# MCU.net
KiCad netlist of a schematic drawn in Altium Designer
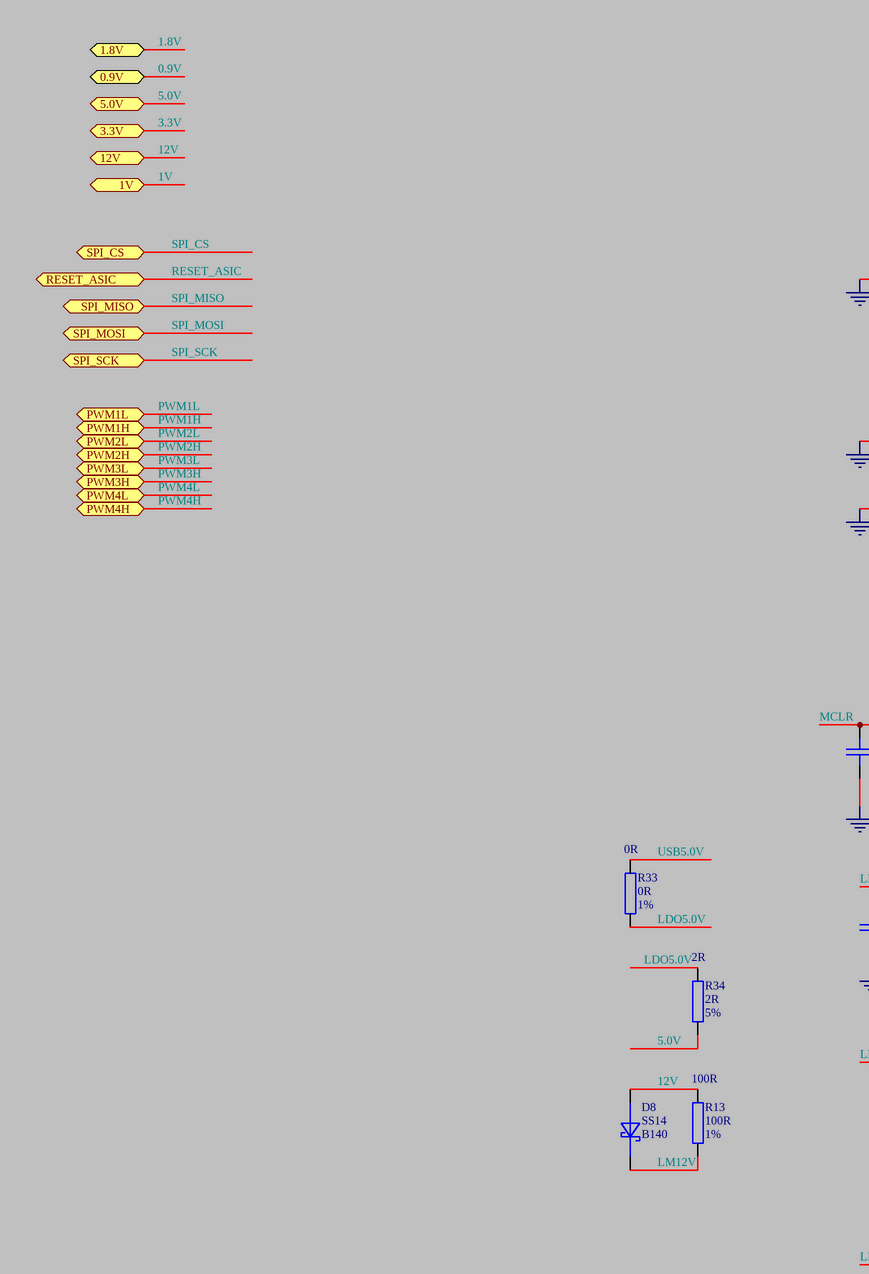
[diagram p0: MCU.SchDoc, left]
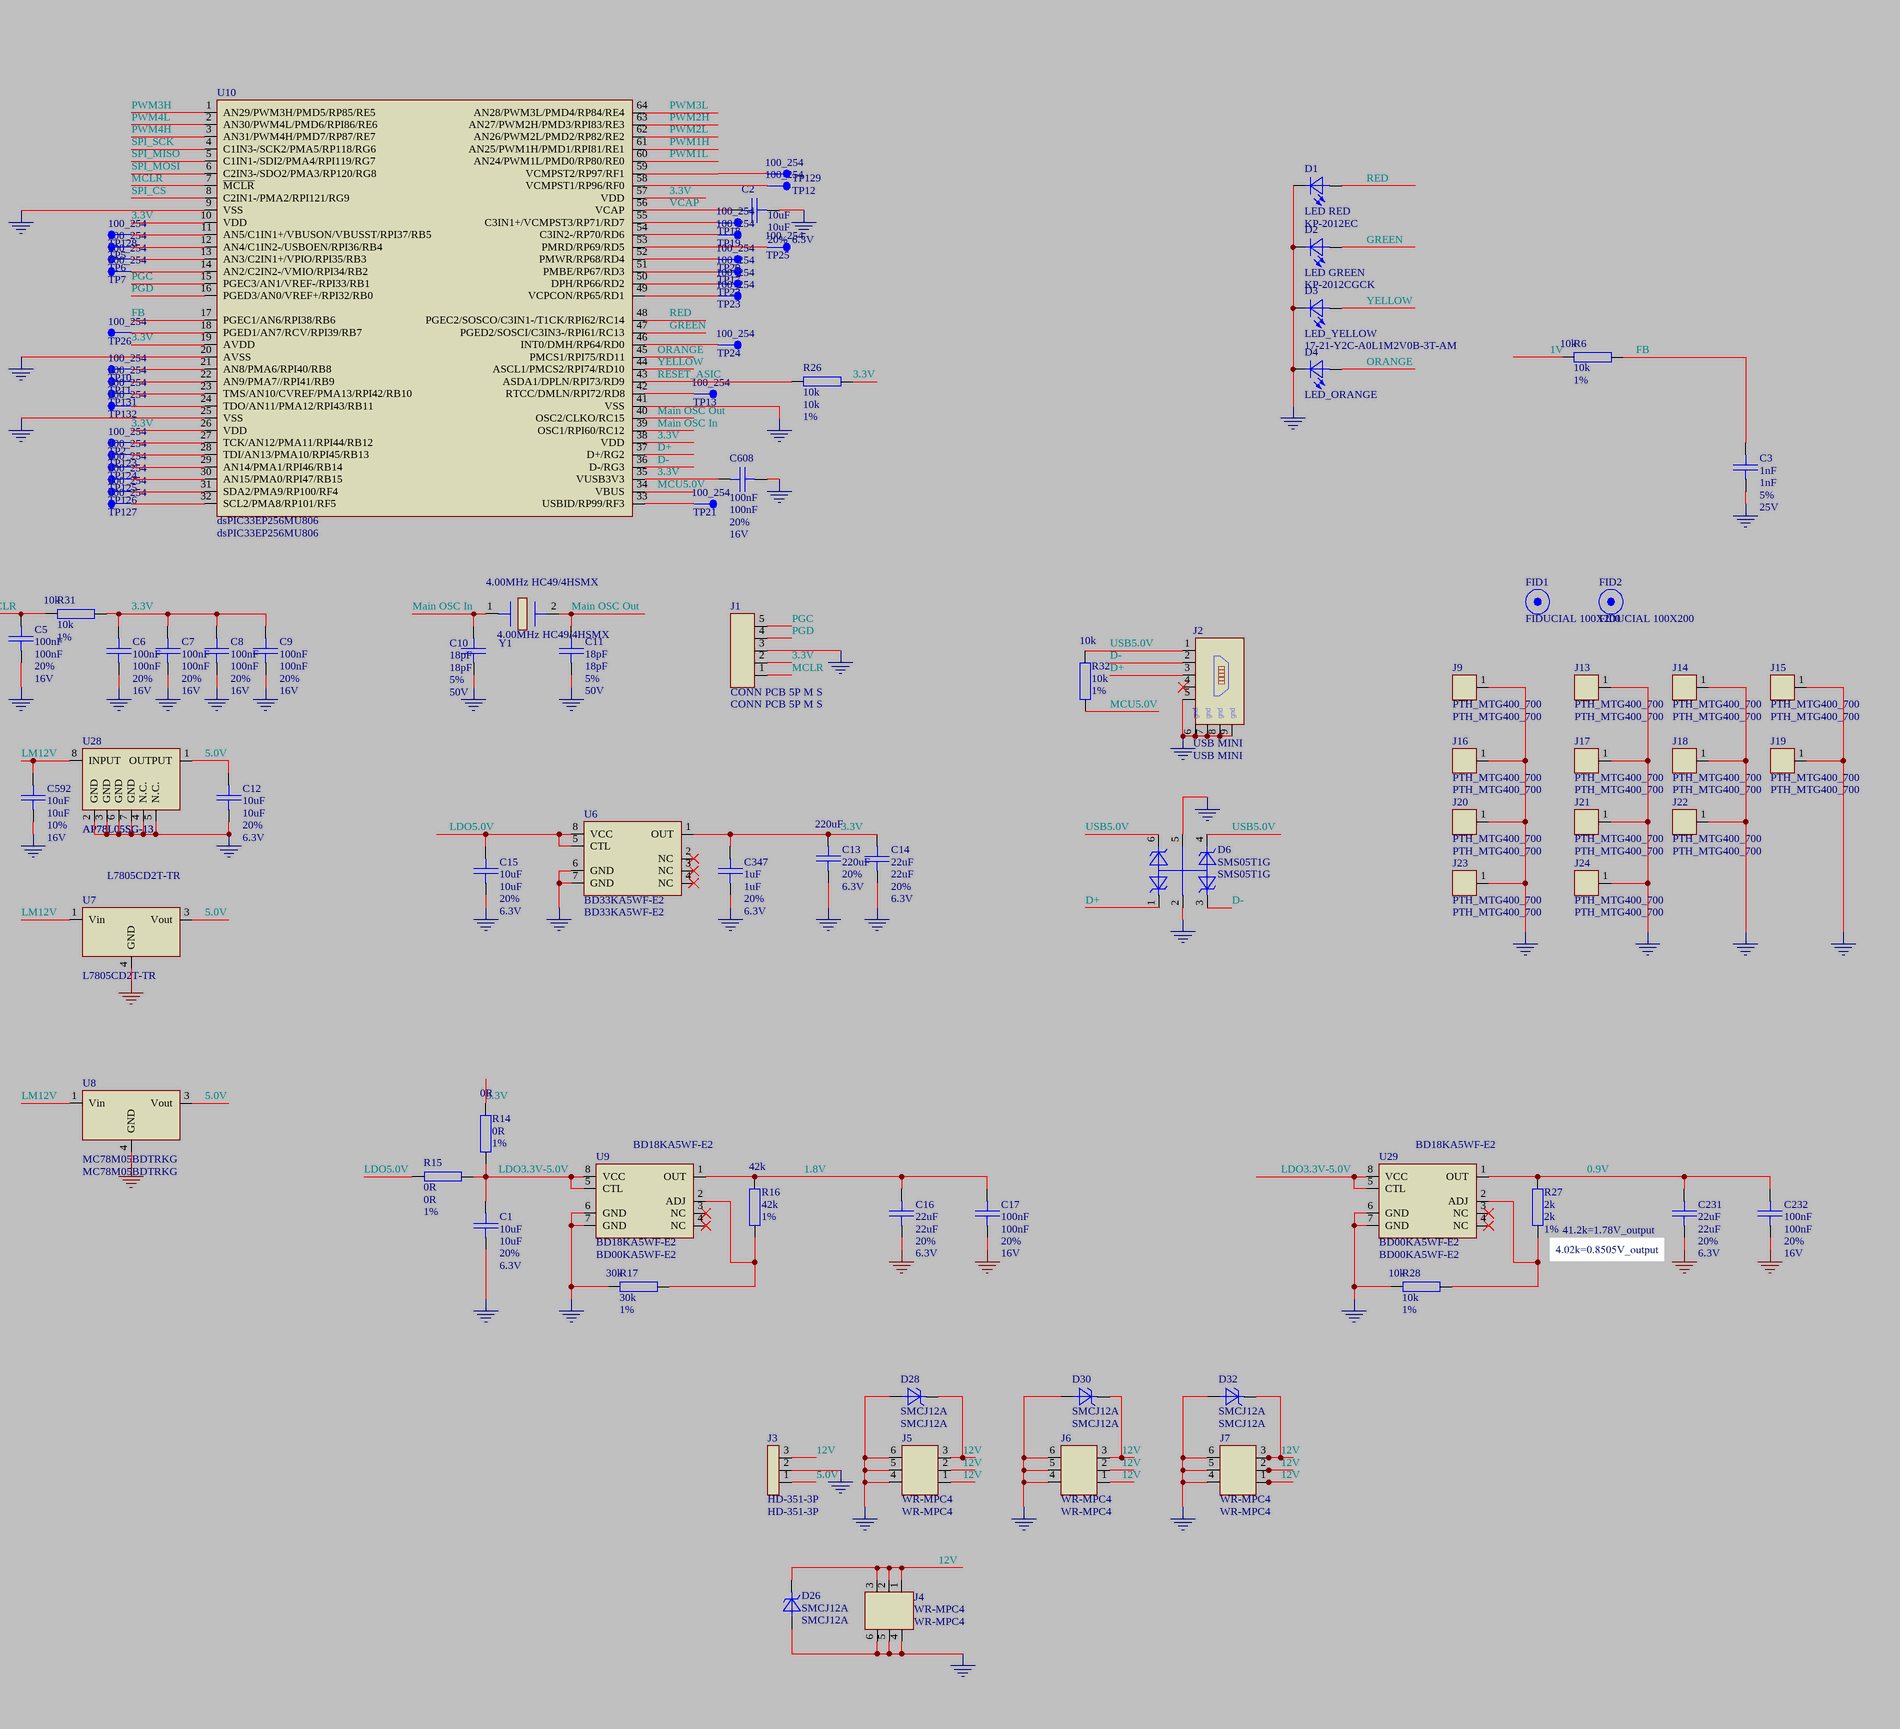
[diagram p1: MCU.SchDoc, right]

(export (version "E")
  (design (tool "Eeschema 10.0.6"))
  (components
    (comp (ref "C1")
      (value "10uF")
      (footprint "SMD_0603_CAPC1608X95N")
      (fields
        (field (name "DB_PART_NUMBER") "CAP000043646")
        (field (name "DB_VALUE") "10uF")
        (field (name "DB_TOLERANCE") "20%")
        (field (name "DB_VOLTAGE") "6.3V")
        (field (name "DB_MANUFACTURER_PART") "KEMET    C0603C106M9PAC")
        (field (name "DB_APPROVED_BY") "ISHIDDEN=T")
      )
      (libsource (lib "Database_Libs1") (part "C"))
    )
    (comp (ref "C2")
      (value "10uF")
      (footprint "SMD_0603_CAPC1608X95N")
      (fields
        (field (name "DB_PART_NUMBER") "CAP000043646")
        (field (name "DB_VALUE") "10uF")
        (field (name "DB_TOLERANCE") "20%")
        (field (name "DB_VOLTAGE") "6.3V")
        (field (name "DB_MANUFACTURER_PART") "KEMET    C0603C106M9PAC")
        (field (name "DB_APPROVED_BY") "ISHIDDEN=T")
      )
      (libsource (lib "Database_Libs1") (part "C"))
    )
    (comp (ref "C3")
      (value "1nF")
      (footprint "SMD_0603_CAPC1608X95N")
      (fields
        (field (name "DB_PART_NUMBER") "CAP000024113")
        (field (name "DB_VALUE") "1nF")
        (field (name "DB_TOLERANCE") "5%")
        (field (name "DB_VOLTAGE") "25V")
        (field (name "DB_MANUFACTURER_PART") "KEMET    C0603C102J3RAC")
        (field (name "DB_APPROVED_BY") "ISHIDDEN=T")
      )
      (libsource (lib "Database_Libs1") (part "C"))
    )
    (comp (ref "C5")
      (value "100nF")
      (footprint "SMD_0603_CAPC1608X95N")
      (fields
        (field (name "DB_PART_NUMBER") "CAP000027236")
        (field (name "DB_VALUE") "100nF")
        (field (name "DB_TOLERANCE") "20%")
        (field (name "DB_VOLTAGE") "16V")
        (field (name "DB_MANUFACTURER_PART") "KEMET    C0603C104M4RAC")
        (field (name "DB_APPROVED_BY") "ISHIDDEN=T")
      )
      (libsource (lib "Database_Libs1") (part "C"))
    )
    (comp (ref "C6")
      (value "100nF")
      (footprint "SMD_0603_CAPC1608X95N")
      (fields
        (field (name "DB_PART_NUMBER") "CAP000027236")
        (field (name "DB_VALUE") "100nF")
        (field (name "DB_TOLERANCE") "20%")
        (field (name "DB_VOLTAGE") "16V")
        (field (name "DB_MANUFACTURER_PART") "KEMET    C0603C104M4RAC")
        (field (name "DB_APPROVED_BY") "ISHIDDEN=T")
      )
      (libsource (lib "Database_Libs1") (part "C"))
    )
    (comp (ref "C7")
      (value "100nF")
      (footprint "SMD_0603_CAPC1608X95N")
      (fields
        (field (name "DB_PART_NUMBER") "CAP000027236")
        (field (name "DB_VALUE") "100nF")
        (field (name "DB_TOLERANCE") "20%")
        (field (name "DB_VOLTAGE") "16V")
        (field (name "DB_MANUFACTURER_PART") "KEMET    C0603C104M4RAC")
        (field (name "DB_APPROVED_BY") "ISHIDDEN=T")
      )
      (libsource (lib "Database_Libs1") (part "C"))
    )
    (comp (ref "C8")
      (value "100nF")
      (footprint "SMD_0603_CAPC1608X95N")
      (fields
        (field (name "DB_PART_NUMBER") "CAP000027236")
        (field (name "DB_VALUE") "100nF")
        (field (name "DB_TOLERANCE") "20%")
        (field (name "DB_VOLTAGE") "16V")
        (field (name "DB_MANUFACTURER_PART") "KEMET    C0603C104M4RAC")
        (field (name "DB_APPROVED_BY") "ISHIDDEN=T")
      )
      (libsource (lib "Database_Libs1") (part "C"))
    )
    (comp (ref "C9")
      (value "100nF")
      (footprint "SMD_0603_CAPC1608X95N")
      (fields
        (field (name "DB_PART_NUMBER") "CAP000027236")
        (field (name "DB_VALUE") "100nF")
        (field (name "DB_TOLERANCE") "20%")
        (field (name "DB_VOLTAGE") "16V")
        (field (name "DB_MANUFACTURER_PART") "KEMET    C0603C104M4RAC")
        (field (name "DB_APPROVED_BY") "ISHIDDEN=T")
      )
      (libsource (lib "Database_Libs1") (part "C"))
    )
    (comp (ref "C10")
      (value "18pF")
      (footprint "SMD_0603_CAPC1608X95N")
      (fields
        (field (name "DB_PART_NUMBER") "CAP000031922")
        (field (name "DB_VALUE") "18pF")
        (field (name "DB_TOLERANCE") "5%")
        (field (name "DB_VOLTAGE") "50V")
        (field (name "DB_MANUFACTURER_PART") "KEMET    C0603C180J5GAC")
        (field (name "DB_APPROVED_BY") "ISHIDDEN=T")
      )
      (libsource (lib "Database_Libs1") (part "C"))
    )
    (comp (ref "C11")
      (value "18pF")
      (footprint "SMD_0603_CAPC1608X95N")
      (fields
        (field (name "DB_PART_NUMBER") "CAP000031922")
        (field (name "DB_VALUE") "18pF")
        (field (name "DB_TOLERANCE") "5%")
        (field (name "DB_VOLTAGE") "50V")
        (field (name "DB_MANUFACTURER_PART") "KEMET    C0603C180J5GAC")
        (field (name "DB_APPROVED_BY") "ISHIDDEN=T")
      )
      (libsource (lib "Database_Libs1") (part "C"))
    )
    (comp (ref "C12")
      (value "10uF")
      (footprint "SMD_0603_CAPC1608X95N")
      (fields
        (field (name "DB_PART_NUMBER") "CAP000043646")
        (field (name "DB_VALUE") "10uF")
        (field (name "DB_TOLERANCE") "20%")
        (field (name "DB_VOLTAGE") "6.3V")
        (field (name "DB_MANUFACTURER_PART") "KEMET    C0603C106M9PAC")
        (field (name "DB_APPROVED_BY") "ISHIDDEN=T")
      )
      (libsource (lib "Database_Libs1") (part "C"))
    )
    (comp (ref "C13")
      (value "220uF")
      (footprint "SMD_1210_CAPC3225X279N")
      (fields
        (field (name "DB_PART_NUMBER") "CAP000047355")
        (field (name "DB_VALUE") "220uF")
        (field (name "DB_TOLERANCE") "20%")
        (field (name "DB_VOLTAGE") "6.3V")
        (field (name "DB_MANUFACTURER_PART") "SAMSUNG    CL32A227MQVNNNE")
        (field (name "DB_APPROVED_BY") "VSN")
      )
      (libsource (lib "Database_Libs1") (part "C"))
    )
    (comp (ref "C14")
      (value "22uF")
      (footprint "SMD_0805_CAPC2012X145N")
      (fields
        (field (name "DB_PART_NUMBER") "CAP000043686")
        (field (name "DB_VALUE") "22uF")
        (field (name "DB_TOLERANCE") "20%")
        (field (name "DB_VOLTAGE") "6.3V")
        (field (name "DB_MANUFACTURER_PART") "KEMET    C0805C226M9PAC")
        (field (name "DB_APPROVED_BY") "ISHIDDEN=T")
      )
      (libsource (lib "Database_Libs1") (part "C"))
    )
    (comp (ref "C15")
      (value "10uF")
      (footprint "SMD_0603_CAPC1608X95N")
      (fields
        (field (name "DB_PART_NUMBER") "CAP000043646")
        (field (name "DB_VALUE") "10uF")
        (field (name "DB_TOLERANCE") "20%")
        (field (name "DB_VOLTAGE") "6.3V")
        (field (name "DB_MANUFACTURER_PART") "KEMET    C0603C106M9PAC")
        (field (name "DB_APPROVED_BY") "ISHIDDEN=T")
      )
      (libsource (lib "Database_Libs1") (part "C"))
    )
    (comp (ref "C16")
      (value "22uF")
      (footprint "SMD_0805_CAPC2012X145N")
      (fields
        (field (name "DB_PART_NUMBER") "CAP000043686")
        (field (name "DB_VALUE") "22uF")
        (field (name "DB_TOLERANCE") "20%")
        (field (name "DB_VOLTAGE") "6.3V")
        (field (name "DB_MANUFACTURER_PART") "KEMET    C0805C226M9PAC")
        (field (name "DB_APPROVED_BY") "ISHIDDEN=T")
      )
      (libsource (lib "Database_Libs1") (part "C"))
    )
    (comp (ref "C17")
      (value "100nF")
      (footprint "SMD_0603_CAPC1608X95N")
      (fields
        (field (name "DB_PART_NUMBER") "CAP000027236")
        (field (name "DB_VALUE") "100nF")
        (field (name "DB_TOLERANCE") "20%")
        (field (name "DB_VOLTAGE") "16V")
        (field (name "DB_MANUFACTURER_PART") "KEMET    C0603C104M4RAC")
        (field (name "DB_APPROVED_BY") "ISHIDDEN=T")
      )
      (libsource (lib "Database_Libs1") (part "C"))
    )
    (comp (ref "C231")
      (value "22uF")
      (footprint "SMD_0805_CAPC2012X145N")
      (fields
        (field (name "DB_PART_NUMBER") "CAP000043686")
        (field (name "DB_VALUE") "22uF")
        (field (name "DB_TOLERANCE") "20%")
        (field (name "DB_VOLTAGE") "6.3V")
        (field (name "DB_MANUFACTURER_PART") "KEMET    C0805C226M9PAC")
        (field (name "DB_APPROVED_BY") "ISHIDDEN=T")
      )
      (libsource (lib "Database_Libs1") (part "C"))
    )
    (comp (ref "C232")
      (value "100nF")
      (footprint "SMD_0603_CAPC1608X95N")
      (fields
        (field (name "DB_PART_NUMBER") "CAP000027236")
        (field (name "DB_VALUE") "100nF")
        (field (name "DB_TOLERANCE") "20%")
        (field (name "DB_VOLTAGE") "16V")
        (field (name "DB_MANUFACTURER_PART") "KEMET    C0603C104M4RAC")
        (field (name "DB_APPROVED_BY") "ISHIDDEN=T")
      )
      (libsource (lib "Database_Libs1") (part "C"))
    )
    (comp (ref "C347")
      (value "1uF")
      (footprint "SMD_0603_CAPC1608X95N")
      (fields
        (field (name "DB_PART_NUMBER") "CAP000043344")
        (field (name "DB_VALUE") "1uF")
        (field (name "DB_TOLERANCE") "20%")
        (field (name "DB_VOLTAGE") "6.3V")
        (field (name "DB_MANUFACTURER_PART") "KEMET    C0603C105M9PAC")
        (field (name "DB_APPROVED_BY") "ISHIDDEN=T")
      )
      (libsource (lib "Database_Libs1") (part "C"))
    )
    (comp (ref "C592")
      (value "10uF")
      (footprint "SMD_0805_CAPC2012X145N")
      (fields
        (field (name "DB_PART_NUMBER") "CAP000043636")
        (field (name "DB_VALUE") "10uF")
        (field (name "DB_TOLERANCE") "10%")
        (field (name "DB_VOLTAGE") "16V")
        (field (name "DB_MANUFACTURER_PART") "KEMET    C0805C106K4PAC")
        (field (name "DB_APPROVED_BY") "ISHIDDEN=T")
      )
      (libsource (lib "Database_Libs1") (part "C"))
    )
    (comp (ref "C608")
      (value "100nF")
      (footprint "SMD_0603_CAPC1608X95N")
      (fields
        (field (name "DB_PART_NUMBER") "CAP000027236")
        (field (name "DB_VALUE") "100nF")
        (field (name "DB_TOLERANCE") "20%")
        (field (name "DB_VOLTAGE") "16V")
        (field (name "DB_MANUFACTURER_PART") "KEMET    C0603C104M4RAC")
        (field (name "DB_APPROVED_BY") "ISHIDDEN=T")
      )
      (libsource (lib "Database_Libs1") (part "C"))
    )
    (comp (ref "D1")
      (value "LED RED")
      (footprint "SMD_0805_LED2012X100N")
      (fields
        (field (name "DB_PART_NUMBER") "OPT000000095")
        (field (name "DB_MANUFACTURER_PART") "KINGBRIGHT       KP-2012EC")
        (field (name "DB_VALUE") "KP-2012EC")
        (field (name "DB_APPROVED_BY") "VSN")
      )
      (libsource (lib "Database_Libs1") (part "LED"))
    )
    (comp (ref "D2")
      (value "LED GREEN")
      (footprint "SMD_0805_LED2012X100N")
      (fields
        (field (name "DB_PART_NUMBER") "OPT000000096")
        (field (name "DB_MANUFACTURER_PART") "KINGBRIGHT       KP-2012CGCK")
        (field (name "DB_VALUE") "KP-2012CGCK")
        (field (name "DB_APPROVED_BY") "VSN")
      )
      (libsource (lib "Database_Libs1") (part "LED"))
    )
    (comp (ref "D3")
      (value "LED_YELLOW")
      (footprint "SMD_0805_LED2012X100N")
      (fields
        (field (name "DB_PART_NUMBER") "OPT000000092")
        (field (name "DB_MANUFACTURER_PART") "EVERLIGHT       17-21-Y2C-A0L1M2V0B-3T-AM")
        (field (name "DB_VALUE") "17-21-Y2C-A0L1M2V0B-3T-AM")
        (field (name "DB_APPROVED_BY") "VSN")
      )
      (libsource (lib "Database_Libs1") (part "LED"))
    )
    (comp (ref "D4")
      (value "LED_ORANGE")
      (footprint "SMD_0805_LED2012X100N")
      (fields
        (field (name "DB_PART_NUMBER") "OPT000000096")
        (field (name "DB_MANUFACTURER_PART") "KINGBRIGHT       KP-2012CGCK")
        (field (name "DB_APPROVED_BY") "VSN")
      )
      (libsource (lib "altium-import") (part "root_0_LED_Orange_"))
    )
    (comp (ref "D6")
      (value "SMS05T1G")
      (footprint "SMD_SOT457_SOT95P275X110-6N")
      (fields
        (field (name "DB_PART_NUMBER") "DDE000002846")
        (field (name "DB_VALUE") "SMS05T1G")
        (field (name "DB_MANUFACTURER_PART") "ON SEMICONDUCTOR        SMS05T1G")
        (field (name "DB_APPROVED_BY") "VSN")
      )
      (libsource (lib "Database_Libs1") (part "D_TVS_QUAD_C1A2C3C4A5C6"))
    )
    (comp (ref "D8")
      (value "SS14")
      (footprint "SMD_DO214AC_SMA")
      (fields
        (field (name "DB_PART_NUMBER") "DDE000000580")
        (field (name "DB_VALUE") "B140")
        (field (name "DB_MANUFACTURER_PART") "Diodes        B140")
        (field (name "DB_APPROVED_BY") "ISHIDDEN=T")
      )
      (libsource (lib "Database_Libs1") (part "D_STKY"))
    )
    (comp (ref "D26")
      (value "SMCJ12A")
      (footprint "SMD_DO214AC_SMC")
      (fields
        (field (name "DB_PART_NUMBER") "DDE000001725")
        (field (name "DB_VALUE") "SMCJ12A")
        (field (name "DB_MANUFACTURER_PART") "Diodes        SMCJ12A")
        (field (name "DB_APPROVED_BY") "ISHIDDEN=T")
      )
      (libsource (lib "Database_Libs1") (part "D_TVS_UNI"))
    )
    (comp (ref "D28")
      (value "SMCJ12A")
      (footprint "SMD_DO214AC_SMC")
      (fields
        (field (name "DB_PART_NUMBER") "DDE000001725")
        (field (name "DB_VALUE") "SMCJ12A")
        (field (name "DB_MANUFACTURER_PART") "Diodes        SMCJ12A")
        (field (name "DB_APPROVED_BY") "ISHIDDEN=T")
      )
      (libsource (lib "Database_Libs1") (part "D_TVS_UNI"))
    )
    (comp (ref "D30")
      (value "SMCJ12A")
      (footprint "SMD_DO214AC_SMC")
      (fields
        (field (name "DB_PART_NUMBER") "DDE000001725")
        (field (name "DB_VALUE") "SMCJ12A")
        (field (name "DB_MANUFACTURER_PART") "Diodes        SMCJ12A")
        (field (name "DB_APPROVED_BY") "ISHIDDEN=T")
      )
      (libsource (lib "Database_Libs1") (part "D_TVS_UNI"))
    )
    (comp (ref "D32")
      (value "SMCJ12A")
      (footprint "SMD_DO214AC_SMC")
      (fields
        (field (name "DB_PART_NUMBER") "DDE000001725")
        (field (name "DB_VALUE") "SMCJ12A")
        (field (name "DB_MANUFACTURER_PART") "Diodes        SMCJ12A")
        (field (name "DB_APPROVED_BY") "ISHIDDEN=T")
      )
      (libsource (lib "Database_Libs1") (part "D_TVS_UNI"))
    )
    (comp (ref "FID1")
      (value "FIDUCIAL 100X200")
      (footprint "FID100X200")
      (fields
        (field (name "DB_PART_NUMBER") "FID000000001")
        (field (name "DB_MANUFACTURER_PART") "ISHIDDEN=T")
        (field (name "DB_APPROVED_BY") "ISHIDDEN=T")
      )
      (libsource (lib "Database_Libs1") (part "FIDUCIAL"))
    )
    (comp (ref "FID2")
      (value "FIDUCIAL 100X200")
      (footprint "FID100X200")
      (fields
        (field (name "DB_PART_NUMBER") "FID000000001")
        (field (name "DB_MANUFACTURER_PART") "ISHIDDEN=T")
        (field (name "DB_APPROVED_BY") "ISHIDDEN=T")
      )
      (libsource (lib "Database_Libs1") (part "FIDUCIAL"))
    )
    (comp (ref "J1")
      (value "CONN PCB 5P M S")
      (footprint "PTH_HDRV05W64P254_1X05")
      (fields
        (field (name "DB_PART_NUMBER") "CON000000006")
        (field (name "DB_VALUE") "CONN PCB 5P M S")
        (field (name "DB_MANUFACTURER_PART") "W+P        143-12-005-00")
        (field (name "DB_APPROVED_BY") "VSN")
      )
      (libsource (lib "Database_Libs1") (part "CON_5PINS"))
    )
    (comp (ref "J2")
      (value "USB MINI")
      (footprint "SMD_CON-CVILUX-CU04-SCM15B0")
      (fields
        (field (name "DB_PART_NUMBER") "CON000000048")
        (field (name "DB_VALUE") "USB MINI")
        (field (name "DB_MANUFACTURER_PART") "CVILUX       CU04-SCM15B0-R0-LF")
        (field (name "DB_APPROVED_BY") "VSN")
      )
      (libsource (lib "Database_Libs1") (part "CON_USB_MINI_1"))
    )
    (comp (ref "J3")
      (value "HD-351-3P")
      (footprint "PTH_CON_HD-351-3P")
      (fields
        (field (name "DB_PART_NUMBER") "CON000000272")
        (field (name "DB_VALUE") "HD-351-3P")
        (field (name "DB_MANUFACTURER_PART") "HOW DER      HD-351-3P")
        (field (name "DB_APPROVED_BY") "VSN")
      )
      (libsource (lib "Database_Libs1") (part "CON_3PINS"))
    )
    (comp (ref "J4")
      (value "WR-MPC4")
      (footprint "PTH_CON_WR-MRC4-6P")
      (fields
        (field (name "DB_PART_NUMBER") "CON000000271")
        (field (name "DB_VALUE") "WR-MPC4")
        (field (name "DB_MANUFACTURER_PART") "WE         649 006 295 22")
        (field (name "DB_APPROVED_BY") "VSN")
      )
      (libsource (lib "") (part "CON_2ROWS_6PINS_1_1"))
    )
    (comp (ref "J5")
      (value "WR-MPC4")
      (footprint "PTH_CON_WR-MRC4-6P")
      (fields
        (field (name "DB_PART_NUMBER") "CON000000271")
        (field (name "DB_VALUE") "WR-MPC4")
        (field (name "DB_MANUFACTURER_PART") "WE         649 006 295 22")
        (field (name "DB_APPROVED_BY") "VSN")
      )
      (libsource (lib "Database_Libs1") (part "CON_2ROWS_6PINS_1"))
    )
    (comp (ref "J6")
      (value "WR-MPC4")
      (footprint "PTH_CON_WR-MRC4-6P")
      (fields
        (field (name "DB_PART_NUMBER") "CON000000271")
        (field (name "DB_VALUE") "WR-MPC4")
        (field (name "DB_MANUFACTURER_PART") "WE         649 006 295 22")
        (field (name "DB_APPROVED_BY") "VSN")
      )
      (libsource (lib "Database_Libs1") (part "CON_2ROWS_6PINS_1"))
    )
    (comp (ref "J7")
      (value "WR-MPC4")
      (footprint "PTH_CON_WR-MRC4-6P")
      (fields
        (field (name "DB_PART_NUMBER") "CON000000271")
        (field (name "DB_VALUE") "WR-MPC4")
        (field (name "DB_MANUFACTURER_PART") "WE         649 006 295 22")
        (field (name "DB_APPROVED_BY") "VSN")
      )
      (libsource (lib "Database_Libs1") (part "CON_2ROWS_6PINS_1"))
    )
    (comp (ref "J9")
      (value "PTH_MTG400_700")
      (footprint "PTH_MTG400_700")
      (fields
        (field (name "DB_PART_NUMBER") "MTH000000030")
        (field (name "DB_VALUE") "PTH_MTG400_700")
        (field (name "DB_APPROVED_BY") "VSN")
      )
      (libsource (lib "Database_Libs1") (part "CON_1PIN"))
    )
    (comp (ref "J13")
      (value "PTH_MTG400_700")
      (footprint "PTH_MTG400_700")
      (fields
        (field (name "DB_PART_NUMBER") "MTH000000030")
        (field (name "DB_VALUE") "PTH_MTG400_700")
        (field (name "DB_APPROVED_BY") "VSN")
      )
      (libsource (lib "Database_Libs1") (part "CON_1PIN"))
    )
    (comp (ref "J14")
      (value "PTH_MTG400_700")
      (footprint "PTH_MTG400_700")
      (fields
        (field (name "DB_PART_NUMBER") "MTH000000030")
        (field (name "DB_VALUE") "PTH_MTG400_700")
        (field (name "DB_APPROVED_BY") "VSN")
      )
      (libsource (lib "Database_Libs1") (part "CON_1PIN"))
    )
    (comp (ref "J15")
      (value "PTH_MTG400_700")
      (footprint "PTH_MTG400_700")
      (fields
        (field (name "DB_PART_NUMBER") "MTH000000030")
        (field (name "DB_VALUE") "PTH_MTG400_700")
        (field (name "DB_APPROVED_BY") "VSN")
      )
      (libsource (lib "Database_Libs1") (part "CON_1PIN"))
    )
    (comp (ref "J16")
      (value "PTH_MTG400_700")
      (footprint "PTH_MTG400_700")
      (fields
        (field (name "DB_PART_NUMBER") "MTH000000030")
        (field (name "DB_VALUE") "PTH_MTG400_700")
        (field (name "DB_APPROVED_BY") "VSN")
      )
      (libsource (lib "Database_Libs1") (part "CON_1PIN"))
    )
    (comp (ref "J17")
      (value "PTH_MTG400_700")
      (footprint "PTH_MTG400_700")
      (fields
        (field (name "DB_PART_NUMBER") "MTH000000030")
        (field (name "DB_VALUE") "PTH_MTG400_700")
        (field (name "DB_APPROVED_BY") "VSN")
      )
      (libsource (lib "Database_Libs1") (part "CON_1PIN"))
    )
    (comp (ref "J18")
      (value "PTH_MTG400_700")
      (footprint "PTH_MTG400_700")
      (fields
        (field (name "DB_PART_NUMBER") "MTH000000030")
        (field (name "DB_VALUE") "PTH_MTG400_700")
        (field (name "DB_APPROVED_BY") "VSN")
      )
      (libsource (lib "Database_Libs1") (part "CON_1PIN"))
    )
    (comp (ref "J19")
      (value "PTH_MTG400_700")
      (footprint "PTH_MTG400_700")
      (fields
        (field (name "DB_PART_NUMBER") "MTH000000030")
        (field (name "DB_VALUE") "PTH_MTG400_700")
        (field (name "DB_APPROVED_BY") "VSN")
      )
      (libsource (lib "Database_Libs1") (part "CON_1PIN"))
    )
    (comp (ref "J20")
      (value "PTH_MTG400_700")
      (footprint "PTH_MTG400_700")
      (fields
        (field (name "DB_PART_NUMBER") "MTH000000030")
        (field (name "DB_VALUE") "PTH_MTG400_700")
        (field (name "DB_APPROVED_BY") "VSN")
      )
      (libsource (lib "Database_Libs1") (part "CON_1PIN"))
    )
    (comp (ref "J21")
      (value "PTH_MTG400_700")
      (footprint "PTH_MTG400_700")
      (fields
        (field (name "DB_PART_NUMBER") "MTH000000030")
        (field (name "DB_VALUE") "PTH_MTG400_700")
        (field (name "DB_APPROVED_BY") "VSN")
      )
      (libsource (lib "Database_Libs1") (part "CON_1PIN"))
    )
    (comp (ref "J22")
      (value "PTH_MTG400_700")
      (footprint "PTH_MTG400_700")
      (fields
        (field (name "DB_PART_NUMBER") "MTH000000030")
        (field (name "DB_VALUE") "PTH_MTG400_700")
        (field (name "DB_APPROVED_BY") "VSN")
      )
      (libsource (lib "Database_Libs1") (part "CON_1PIN"))
    )
    (comp (ref "J23")
      (value "PTH_MTG400_700")
      (footprint "PTH_MTG400_700")
      (fields
        (field (name "DB_PART_NUMBER") "MTH000000030")
        (field (name "DB_VALUE") "PTH_MTG400_700")
        (field (name "DB_APPROVED_BY") "VSN")
      )
      (libsource (lib "Database_Libs1") (part "CON_1PIN"))
    )
    (comp (ref "J24")
      (value "PTH_MTG400_700")
      (footprint "PTH_MTG400_700")
      (fields
        (field (name "DB_PART_NUMBER") "MTH000000030")
        (field (name "DB_VALUE") "PTH_MTG400_700")
        (field (name "DB_APPROVED_BY") "VSN")
      )
      (libsource (lib "Database_Libs1") (part "CON_1PIN"))
    )
    (comp (ref "R6")
      (value "10k")
      (footprint "SMD_0603_RESC1608X55N")
      (fields
        (field (name "DB_PART_NUMBER") "RES000008663")
        (field (name "DB_VALUE") "10k")
        (field (name "DB_TOLERANCE") "1%")
        (field (name "DB_MANUFACTURER_PART") "YAGEO    RC0603FR-0710KL")
        (field (name "DB_APPROVED_BY") "VSN")
      )
      (libsource (lib "Database_Libs1") (part "R"))
    )
    (comp (ref "R13")
      (value "100R")
      (footprint "SMD_1206_RESC3216X65N")
      (fields
        (field (name "DB_PART_NUMBER") "RES000006922")
        (field (name "DB_VALUE") "100R")
        (field (name "DB_TOLERANCE") "1%")
        (field (name "DB_MANUFACTURER_PART") "YAGEO    RC1206FR-07100R")
        (field (name "DB_APPROVED_BY") "ISHIDDEN=T")
      )
      (libsource (lib "Database_Libs1") (part "R"))
    )
    (comp (ref "R14")
      (value "0R")
      (footprint "SMD_1206_RESC3216X65N")
      (fields
        (field (name "DB_PART_NUMBER") "RES000008756")
        (field (name "DB_VALUE") "0R")
        (field (name "DB_TOLERANCE") "1%")
        (field (name "DB_MANUFACTURER_PART") "YAGEO    AC1206FR-070RL")
        (field (name "DB_APPROVED_BY") "VSN")
      )
      (libsource (lib "Database_Libs1") (part "R"))
    )
    (comp (ref "R15")
      (value "0R")
      (footprint "SMD_1206_RESC3216X65N")
      (fields
        (field (name "DB_PART_NUMBER") "RES000008756")
        (field (name "DB_VALUE") "0R")
        (field (name "DB_TOLERANCE") "1%")
        (field (name "DB_MANUFACTURER_PART") "YAGEO    AC1206FR-070RL")
        (field (name "DB_APPROVED_BY") "VSN")
      )
      (libsource (lib "Database_Libs1") (part "R"))
    )
    (comp (ref "R16")
      (value "42k")
      (footprint "SMD_0603_RESC1608X55N")
      (fields
        (field (name "DB_PART_NUMBER") "RES000001590")
        (field (name "DB_VALUE") "42k")
        (field (name "DB_TOLERANCE") "1%")
        (field (name "DB_MANUFACTURER_PART") "YAGEO    RC0603FR-0741K2")
        (field (name "DB_APPROVED_BY") "ISHIDDEN=T")
      )
      (libsource (lib "Schlib1") (part "R_42k"))
    )
    (comp (ref "R17")
      (value "30k")
      (footprint "SMD_0603_RESC1608X55N")
      (fields
        (field (name "DB_PART_NUMBER") "RES000006287")
        (field (name "DB_VALUE") "30k")
        (field (name "DB_TOLERANCE") "1%")
        (field (name "DB_MANUFACTURER_PART") "YAGEO    RC0603FR-0730K")
        (field (name "DB_APPROVED_BY") "ISHIDDEN=T")
      )
      (libsource (lib "Database_Libs1") (part "R"))
    )
    (comp (ref "R26")
      (value "10k")
      (footprint "SMD_0603_RESC1608X55N")
      (fields
        (field (name "DB_PART_NUMBER") "RES000008663")
        (field (name "DB_VALUE") "10k")
        (field (name "DB_TOLERANCE") "1%")
        (field (name "DB_MANUFACTURER_PART") "YAGEO    RC0603FR-0710KL")
        (field (name "DB_APPROVED_BY") "VSN")
      )
      (libsource (lib "Database_Libs1") (part "R"))
    )
    (comp (ref "R27")
      (value "2k")
      (footprint "SMD_0603_RESC1608X55N")
      (fields
        (field (name "DB_PART_NUMBER") "RES000008586")
        (field (name "DB_VALUE") "2k")
        (field (name "DB_TOLERANCE") "1%")
        (field (name "DB_MANUFACTURER_PART") "YAGEO       AC0603FR-072KL")
        (field (name "DB_APPROVED_BY") "VSN")
      )
      (libsource (lib "Database_Libs1") (part "R"))
    )
    (comp (ref "R28")
      (value "10k")
      (footprint "SMD_0603_RESC1608X55N")
      (fields
        (field (name "DB_PART_NUMBER") "RES000008663")
        (field (name "DB_VALUE") "10k")
        (field (name "DB_TOLERANCE") "1%")
        (field (name "DB_MANUFACTURER_PART") "YAGEO    RC0603FR-0710KL")
        (field (name "DB_APPROVED_BY") "VSN")
      )
      (libsource (lib "Database_Libs1") (part "R"))
    )
    (comp (ref "R31")
      (value "10k")
      (footprint "SMD_0603_RESC1608X55N")
      (fields
        (field (name "DB_PART_NUMBER") "RES000008663")
        (field (name "DB_VALUE") "10k")
        (field (name "DB_TOLERANCE") "1%")
        (field (name "DB_MANUFACTURER_PART") "YAGEO    RC0603FR-0710KL")
        (field (name "DB_APPROVED_BY") "VSN")
      )
      (libsource (lib "Database_Libs1") (part "R"))
    )
    (comp (ref "R32")
      (value "10k")
      (footprint "SMD_0603_RESC1608X55N")
      (fields
        (field (name "DB_PART_NUMBER") "RES000008663")
        (field (name "DB_VALUE") "10k")
        (field (name "DB_TOLERANCE") "1%")
        (field (name "DB_MANUFACTURER_PART") "YAGEO    RC0603FR-0710KL")
        (field (name "DB_APPROVED_BY") "VSN")
      )
      (libsource (lib "Database_Libs1") (part "R"))
    )
    (comp (ref "R33")
      (value "0R")
      (footprint "SMD_0603_RESC1608X55N")
      (fields
        (field (name "DB_PART_NUMBER") "RES000008926")
        (field (name "DB_VALUE") "0R")
        (field (name "DB_TOLERANCE") "1%")
        (field (name "DB_MANUFACTURER_PART") "YAGEO    AC0603FR-070RL")
        (field (name "DB_APPROVED_BY") "VSN")
      )
      (libsource (lib "Database_Libs1") (part "R"))
    )
    (comp (ref "R34")
      (value "2R")
      (footprint "SMD_1206_RESC3216X65N")
      (fields
        (field (name "DB_PART_NUMBER") "RES000007051")
        (field (name "DB_VALUE") "2R")
        (field (name "DB_TOLERANCE") "5%")
        (field (name "DB_MANUFACTURER_PART") "YAGEO    RC1206JR-072R")
        (field (name "DB_APPROVED_BY") "ISHIDDEN=T")
      )
      (libsource (lib "Database_Libs1") (part "R"))
    )
    (comp (ref "TP2")
      (value "100_254")
      (footprint "SMD_TP_100-254")
      (fields
        (field (name "DB_PART_NUMBER") "TPO000000001")
        (field (name "DB_MANUFACTURER_PART") "ISHIDDEN=T")
        (field (name "DB_APPROVED_BY") "ISHIDDEN=T")
      )
      (libsource (lib "Database_Libs1") (part "TEST_POINT_1"))
    )
    (comp (ref "TP5")
      (value "100_254")
      (footprint "SMD_TP_100-254")
      (fields
        (field (name "DB_PART_NUMBER") "TPO000000001")
        (field (name "DB_MANUFACTURER_PART") "ISHIDDEN=T")
        (field (name "DB_APPROVED_BY") "ISHIDDEN=T")
      )
      (libsource (lib "Database_Libs1") (part "TEST_POINT_1"))
    )
    (comp (ref "TP6")
      (value "100_254")
      (footprint "SMD_TP_100-254")
      (fields
        (field (name "DB_PART_NUMBER") "TPO000000001")
        (field (name "DB_MANUFACTURER_PART") "ISHIDDEN=T")
        (field (name "DB_APPROVED_BY") "ISHIDDEN=T")
      )
      (libsource (lib "Database_Libs1") (part "TEST_POINT_1"))
    )
    (comp (ref "TP7")
      (value "100_254")
      (footprint "SMD_TP_100-254")
      (fields
        (field (name "DB_PART_NUMBER") "TPO000000001")
        (field (name "DB_MANUFACTURER_PART") "ISHIDDEN=T")
        (field (name "DB_APPROVED_BY") "ISHIDDEN=T")
      )
      (libsource (lib "Database_Libs1") (part "TEST_POINT_1"))
    )
    (comp (ref "TP10")
      (value "100_254")
      (footprint "SMD_TP_100-254")
      (fields
        (field (name "DB_PART_NUMBER") "TPO000000001")
        (field (name "DB_MANUFACTURER_PART") "ISHIDDEN=T")
        (field (name "DB_APPROVED_BY") "ISHIDDEN=T")
      )
      (libsource (lib "Database_Libs1") (part "TEST_POINT_1"))
    )
    (comp (ref "TP11")
      (value "100_254")
      (footprint "SMD_TP_100-254")
      (fields
        (field (name "DB_PART_NUMBER") "TPO000000001")
        (field (name "DB_MANUFACTURER_PART") "ISHIDDEN=T")
        (field (name "DB_APPROVED_BY") "ISHIDDEN=T")
      )
      (libsource (lib "Database_Libs1") (part "TEST_POINT_1"))
    )
    (comp (ref "TP12")
      (value "100_254")
      (footprint "SMD_TP_100-254")
      (fields
        (field (name "DB_PART_NUMBER") "TPO000000001")
        (field (name "DB_MANUFACTURER_PART") "ISHIDDEN=T")
        (field (name "DB_APPROVED_BY") "ISHIDDEN=T")
      )
      (libsource (lib "Database_Libs1") (part "TEST_POINT_1"))
    )
    (comp (ref "TP13")
      (value "100_254")
      (footprint "SMD_TP_100-254")
      (fields
        (field (name "DB_PART_NUMBER") "TPO000000001")
        (field (name "DB_MANUFACTURER_PART") "ISHIDDEN=T")
        (field (name "DB_APPROVED_BY") "ISHIDDEN=T")
      )
      (libsource (lib "Database_Libs1") (part "TEST_POINT_1"))
    )
    (comp (ref "TP17")
      (value "100_254")
      (footprint "SMD_TP_100-254")
      (fields
        (field (name "DB_PART_NUMBER") "TPO000000001")
        (field (name "DB_MANUFACTURER_PART") "ISHIDDEN=T")
        (field (name "DB_APPROVED_BY") "ISHIDDEN=T")
      )
      (libsource (lib "Database_Libs1") (part "TEST_POINT_1"))
    )
    (comp (ref "TP18")
      (value "100_254")
      (footprint "SMD_TP_100-254")
      (fields
        (field (name "DB_PART_NUMBER") "TPO000000001")
        (field (name "DB_MANUFACTURER_PART") "ISHIDDEN=T")
        (field (name "DB_APPROVED_BY") "ISHIDDEN=T")
      )
      (libsource (lib "Database_Libs1") (part "TEST_POINT_1"))
    )
    (comp (ref "TP19")
      (value "100_254")
      (footprint "SMD_TP_100-254")
      (fields
        (field (name "DB_PART_NUMBER") "TPO000000001")
        (field (name "DB_MANUFACTURER_PART") "ISHIDDEN=T")
        (field (name "DB_APPROVED_BY") "ISHIDDEN=T")
      )
      (libsource (lib "Database_Libs1") (part "TEST_POINT_1"))
    )
    (comp (ref "TP20")
      (value "100_254")
      (footprint "SMD_TP_100-254")
      (fields
        (field (name "DB_PART_NUMBER") "TPO000000001")
        (field (name "DB_MANUFACTURER_PART") "ISHIDDEN=T")
        (field (name "DB_APPROVED_BY") "ISHIDDEN=T")
      )
      (libsource (lib "Database_Libs1") (part "TEST_POINT_1"))
    )
    (comp (ref "TP21")
      (value "100_254")
      (footprint "SMD_TP_100-254")
      (fields
        (field (name "DB_PART_NUMBER") "TPO000000001")
        (field (name "DB_MANUFACTURER_PART") "ISHIDDEN=T")
        (field (name "DB_APPROVED_BY") "ISHIDDEN=T")
      )
      (libsource (lib "Database_Libs1") (part "TEST_POINT_1"))
    )
    (comp (ref "TP22")
      (value "100_254")
      (footprint "SMD_TP_100-254")
      (fields
        (field (name "DB_PART_NUMBER") "TPO000000001")
        (field (name "DB_MANUFACTURER_PART") "ISHIDDEN=T")
        (field (name "DB_APPROVED_BY") "ISHIDDEN=T")
      )
      (libsource (lib "Database_Libs1") (part "TEST_POINT_1"))
    )
    (comp (ref "TP23")
      (value "100_254")
      (footprint "SMD_TP_100-254")
      (fields
        (field (name "DB_PART_NUMBER") "TPO000000001")
        (field (name "DB_MANUFACTURER_PART") "ISHIDDEN=T")
        (field (name "DB_APPROVED_BY") "ISHIDDEN=T")
      )
      (libsource (lib "Database_Libs1") (part "TEST_POINT_1"))
    )
    (comp (ref "TP24")
      (value "100_254")
      (footprint "SMD_TP_100-254")
      (fields
        (field (name "DB_PART_NUMBER") "TPO000000001")
        (field (name "DB_MANUFACTURER_PART") "ISHIDDEN=T")
        (field (name "DB_APPROVED_BY") "ISHIDDEN=T")
      )
      (libsource (lib "Database_Libs1") (part "TEST_POINT_1"))
    )
    (comp (ref "TP25")
      (value "100_254")
      (footprint "SMD_TP_100-254")
      (fields
        (field (name "DB_PART_NUMBER") "TPO000000001")
        (field (name "DB_MANUFACTURER_PART") "ISHIDDEN=T")
        (field (name "DB_APPROVED_BY") "ISHIDDEN=T")
      )
      (libsource (lib "Database_Libs1") (part "TEST_POINT_1"))
    )
    (comp (ref "TP26")
      (value "100_254")
      (footprint "SMD_TP_100-254")
      (fields
        (field (name "DB_PART_NUMBER") "TPO000000001")
        (field (name "DB_MANUFACTURER_PART") "ISHIDDEN=T")
        (field (name "DB_APPROVED_BY") "ISHIDDEN=T")
      )
      (libsource (lib "Database_Libs1") (part "TEST_POINT_1"))
    )
    (comp (ref "TP123")
      (value "100_254")
      (footprint "SMD_TP_100-254")
      (fields
        (field (name "DB_PART_NUMBER") "TPO000000001")
        (field (name "DB_MANUFACTURER_PART") "ISHIDDEN=T")
        (field (name "DB_APPROVED_BY") "ISHIDDEN=T")
      )
      (libsource (lib "Database_Libs1") (part "TEST_POINT_1"))
    )
    (comp (ref "TP124")
      (value "100_254")
      (footprint "SMD_TP_100-254")
      (fields
        (field (name "DB_PART_NUMBER") "TPO000000001")
        (field (name "DB_MANUFACTURER_PART") "ISHIDDEN=T")
        (field (name "DB_APPROVED_BY") "ISHIDDEN=T")
      )
      (libsource (lib "Database_Libs1") (part "TEST_POINT_1"))
    )
    (comp (ref "TP125")
      (value "100_254")
      (footprint "SMD_TP_100-254")
      (fields
        (field (name "DB_PART_NUMBER") "TPO000000001")
        (field (name "DB_MANUFACTURER_PART") "ISHIDDEN=T")
        (field (name "DB_APPROVED_BY") "ISHIDDEN=T")
      )
      (libsource (lib "Database_Libs1") (part "TEST_POINT_1"))
    )
    (comp (ref "TP126")
      (value "100_254")
      (footprint "SMD_TP_100-254")
      (fields
        (field (name "DB_PART_NUMBER") "TPO000000001")
        (field (name "DB_MANUFACTURER_PART") "ISHIDDEN=T")
        (field (name "DB_APPROVED_BY") "ISHIDDEN=T")
      )
      (libsource (lib "Database_Libs1") (part "TEST_POINT_1"))
    )
    (comp (ref "TP127")
      (value "100_254")
      (footprint "SMD_TP_100-254")
      (fields
        (field (name "DB_PART_NUMBER") "TPO000000001")
        (field (name "DB_MANUFACTURER_PART") "ISHIDDEN=T")
        (field (name "DB_APPROVED_BY") "ISHIDDEN=T")
      )
      (libsource (lib "Database_Libs1") (part "TEST_POINT_1"))
    )
    (comp (ref "TP128")
      (value "100_254")
      (footprint "SMD_TP_100-254")
      (fields
        (field (name "DB_PART_NUMBER") "TPO000000001")
        (field (name "DB_MANUFACTURER_PART") "ISHIDDEN=T")
        (field (name "DB_APPROVED_BY") "ISHIDDEN=T")
      )
      (libsource (lib "Database_Libs1") (part "TEST_POINT_1"))
    )
    (comp (ref "TP129")
      (value "100_254")
      (footprint "SMD_TP_100-254")
      (fields
        (field (name "DB_PART_NUMBER") "TPO000000001")
        (field (name "DB_MANUFACTURER_PART") "ISHIDDEN=T")
        (field (name "DB_APPROVED_BY") "ISHIDDEN=T")
      )
      (libsource (lib "Database_Libs1") (part "TEST_POINT_1"))
    )
    (comp (ref "TP131")
      (value "100_254")
      (footprint "SMD_TP_100-254")
      (fields
        (field (name "DB_PART_NUMBER") "TPO000000001")
        (field (name "DB_MANUFACTURER_PART") "ISHIDDEN=T")
        (field (name "DB_APPROVED_BY") "ISHIDDEN=T")
      )
      (libsource (lib "Database_Libs1") (part "TEST_POINT_1"))
    )
    (comp (ref "TP132")
      (value "100_254")
      (footprint "SMD_TP_100-254")
      (fields
        (field (name "DB_PART_NUMBER") "TPO000000001")
        (field (name "DB_MANUFACTURER_PART") "ISHIDDEN=T")
        (field (name "DB_APPROVED_BY") "ISHIDDEN=T")
      )
      (libsource (lib "Database_Libs1") (part "TEST_POINT_1"))
    )
    (comp (ref "U6")
      (value "BD33KA5WF-E2")
      (footprint "SMD_SOIC127P620X160-8N")
      (fields
        (field (name "DB_PART_NUMBER") "PSU000000127")
        (field (name "DB_VALUE") "BD33KA5WF-E2")
        (field (name "DB_MANUFACTURER_PART") "ROHM        BD33KA5WF-E2")
        (field (name "DB_APPROVED_BY") "VSN")
      )
      (libsource (lib "Database_Libs1") (part "IC_BDXXKA5WF"))
    )
    (comp (ref "U7")
      (value "L7805CD2T-TR")
      (footprint "SMD_TO254P1542X460-3_4N")
      (fields
        (field (name "DB_PART_NUMBER") "PSU000000129")
        (field (name "DB_VALUE") "L7805CD2T-TR")
        (field (name "DB_MANUFACTURER_PART") "ST       L7805CD2T-TR")
        (field (name "DB_APPROVED_BY") "VSN")
      )
      (libsource (lib "Database_Libs1") (part "IC_IN1OUT3GND4"))
    )
    (comp (ref "U8")
      (value "MC78M05BDTRKG")
      (footprint "SMD_TO229P991X239-4N_DPAK")
      (fields
        (field (name "DB_PART_NUMBER") "PSU000000031")
        (field (name "DB_VALUE") "MC78M05BDTRKG")
        (field (name "DB_MANUFACTURER_PART") "ON Semiconductor       MC78M05BDTRKG")
        (field (name "DB_APPROVED_BY") "VSN")
      )
      (libsource (lib "Database_Libs1") (part "IC_VIN1GND4VOUT3"))
    )
    (comp (ref "U9")
      (value "BD18KA5WF-E2")
      (footprint "SMD_SOIC127P620X160-8N")
      (fields
        (field (name "DB_PART_NUMBER") "PSU000000128")
        (field (name "DB_VALUE") "BD00KA5WF-E2")
        (field (name "DB_MANUFACTURER_PART") "ROHM        BD00KA5WF-E2")
        (field (name "DB_APPROVED_BY") "VSN")
      )
      (libsource (lib "Database_Libs1") (part "IC_BD00KA5WF"))
    )
    (comp (ref "U10")
      (value "dsPIC33EP256MU806")
      (footprint "SMD_QFP50P1200X1200X120-64N")
      (fields
        (field (name "DB_PART_NUMBER") "MCU000000070")
        (field (name "DB_VALUE") "dsPIC33EP256MU806")
        (field (name "DB_MANUFACTURER_PART") "MICROCHIP        DSPIC33EP256MU806-E/PT")
        (field (name "DB_APPROVED_BY") "VSN")
      )
      (libsource (lib "Database_Libs1") (part "IC_DSPIC33EP256MU806-QFN64"))
    )
    (comp (ref "U28")
      (value "AP78L05SG-13")
      (footprint "SMD_SOIC127P600X175-8N")
      (fields
        (field (name "DB_PART_NUMBER") "PSU000000125")
        (field (name "DB_VALUE") "AP78L05SG-13")
        (field (name "DB_MANUFACTURER_PART") "DIODES        AP78L05SG-13")
        (field (name "DB_APPROVED_BY") "VSN")
      )
      (libsource (lib "Database_Libs1") (part "IC_LM2931AD-5.0R2G_SO-8"))
    )
    (comp (ref "U29")
      (value "BD00KA5WF-E2")
      (footprint "SMD_SOIC127P620X160-8N")
      (fields
        (field (name "DB_PART_NUMBER") "PSU000000128")
        (field (name "DB_VALUE") "BD00KA5WF-E2")
        (field (name "DB_MANUFACTURER_PART") "ROHM        BD00KA5WF-E2")
        (field (name "DB_APPROVED_BY") "VSN")
      )
      (libsource (lib "Database_Libs1") (part "IC_BD00KA5WF"))
    )
    (comp (ref "Y1")
      (value "4.00MHz HC49/4HSMX")
      (footprint "SMD_HC49_XTAL1140X480X420N")
      (fields
        (field (name "DB_PART_NUMBER") "OSC000000012")
        (field (name "DB_VALUE") "4.00MHz HC49/4HSMX")
        (field (name "DB_MANUFACTURER_PART") "IQD       4.00MHz HC49/4HSMX")
        (field (name "DB_APPROVED_BY") "VSN")
      )
      (libsource (lib "Database_Libs1") (part "XTAL"))
    )
  )
  (nets
    (net (code "1") (name "/0.9V") (class "Default")
      (node (ref "C231") (pin "1") (pinfunction "1_1") (pintype "passive"))
      (node (ref "C232") (pin "1") (pinfunction "1_1") (pintype "passive"))
      (node (ref "R27") (pin "1") (pinfunction "1_1") (pintype "passive"))
      (node (ref "U29") (pin "1") (pinfunction "OUT_1") (pintype "passive"))
    )
    (net (code "2") (name "/1.8V") (class "Default")
      (node (ref "C16") (pin "1") (pinfunction "1_1") (pintype "passive"))
      (node (ref "C17") (pin "1") (pinfunction "1_1") (pintype "passive"))
      (node (ref "R16") (pin "1") (pinfunction "1_1") (pintype "passive"))
      (node (ref "U9") (pin "1") (pinfunction "OUT_1") (pintype "passive"))
    )
    (net (code "3") (name "/1V") (class "Default")
      (node (ref "R6") (pin "2") (pinfunction "2_2") (pintype "passive"))
    )
    (net (code "4") (name "/3.3V") (class "Default")
      (node (ref "C13") (pin "2") (pinfunction "2_2") (pintype "passive"))
      (node (ref "C14") (pin "1") (pinfunction "1_1") (pintype "passive"))
      (node (ref "C347") (pin "1") (pinfunction "1_1") (pintype "passive"))
      (node (ref "C6") (pin "1") (pinfunction "1_1") (pintype "passive"))
      (node (ref "C608") (pin "1") (pinfunction "1_1") (pintype "passive"))
      (node (ref "C7") (pin "1") (pinfunction "1_1") (pintype "passive"))
      (node (ref "C8") (pin "1") (pinfunction "1_1") (pintype "passive"))
      (node (ref "C9") (pin "1") (pinfunction "1_1") (pintype "passive"))
      (node (ref "J1") (pin "2") (pinfunction "2_2") (pintype "passive"))
      (node (ref "R14") (pin "2") (pinfunction "2_2") (pintype "passive"))
      (node (ref "R26") (pin "1") (pinfunction "1_1") (pintype "passive"))
      (node (ref "R31") (pin "2") (pinfunction "2_2") (pintype "passive"))
      (node (ref "U10") (pin "10") (pinfunction "VDD_10") (pintype "passive"))
      (node (ref "U10") (pin "19") (pinfunction "AVDD_19") (pintype "passive"))
      (node (ref "U10") (pin "26") (pinfunction "VDD_26") (pintype "passive"))
      (node (ref "U10") (pin "35") (pinfunction "VUSB3V3_35") (pintype "passive"))
      (node (ref "U10") (pin "38") (pinfunction "VDD_38") (pintype "passive"))
      (node (ref "U10") (pin "57") (pinfunction "VDD_57") (pintype "passive"))
      (node (ref "U6") (pin "1") (pinfunction "OUT_1") (pintype "passive"))
    )
    (net (code "5") (name "/5.0V") (class "Default")
      (node (ref "C12") (pin "1") (pinfunction "1_1") (pintype "passive"))
      (node (ref "J3") (pin "1") (pinfunction "1_1") (pintype "passive"))
      (node (ref "R34") (pin "1") (pinfunction "1_1") (pintype "passive"))
      (node (ref "U28") (pin "1") (pinfunction "OUTPUT_1") (pintype "passive"))
      (node (ref "U7") (pin "3") (pinfunction "Vout_3") (pintype "passive"))
      (node (ref "U8") (pin "3") (pinfunction "Vout_3") (pintype "passive"))
    )
    (net (code "6") (name "/12V") (class "Default")
      (node (ref "D26") (pin "1") (pinfunction "C_1") (pintype "passive"))
      (node (ref "D28") (pin "1") (pinfunction "C_1") (pintype "passive"))
      (node (ref "D30") (pin "1") (pinfunction "C_1") (pintype "passive"))
      (node (ref "D32") (pin "1") (pinfunction "C_1") (pintype "passive"))
      (node (ref "D8") (pin "2") (pinfunction "A_2") (pintype "passive"))
      (node (ref "J3") (pin "3") (pinfunction "3_3") (pintype "passive"))
      (node (ref "J4") (pin "1") (pinfunction "1_1") (pintype "passive"))
      (node (ref "J4") (pin "2") (pinfunction "2_2") (pintype "passive"))
      (node (ref "J4") (pin "3") (pinfunction "3_3") (pintype "passive"))
      (node (ref "J5") (pin "1") (pinfunction "1_1") (pintype "passive"))
      (node (ref "J5") (pin "2") (pinfunction "2_2") (pintype "passive"))
      (node (ref "J5") (pin "3") (pinfunction "3_3") (pintype "passive"))
      (node (ref "J6") (pin "1") (pinfunction "1_1") (pintype "passive"))
      (node (ref "J6") (pin "2") (pinfunction "2_2") (pintype "passive"))
      (node (ref "J6") (pin "3") (pinfunction "3_3") (pintype "passive"))
      (node (ref "J7") (pin "1") (pinfunction "1_1") (pintype "passive"))
      (node (ref "J7") (pin "2") (pinfunction "2_2") (pintype "passive"))
      (node (ref "J7") (pin "3") (pinfunction "3_3") (pintype "passive"))
      (node (ref "R13") (pin "2") (pinfunction "2_2") (pintype "passive"))
    )
    (net (code "7") (name "/D+") (class "Default")
      (node (ref "D6") (pin "1") (pinfunction "1_1") (pintype "passive"))
      (node (ref "J2") (pin "3") (pinfunction "3_3") (pintype "passive"))
      (node (ref "U10") (pin "37") (pinfunction "D+/RG2_37") (pintype "passive"))
    )
    (net (code "8") (name "/D-") (class "Default")
      (node (ref "D6") (pin "3") (pinfunction "3_3") (pintype "passive"))
      (node (ref "J2") (pin "2") (pinfunction "2_2") (pintype "passive"))
      (node (ref "U10") (pin "36") (pinfunction "D-/RG3_36") (pintype "passive"))
    )
    (net (code "9") (name "/FB") (class "Default")
      (node (ref "C3") (pin "1") (pinfunction "1_1") (pintype "passive"))
      (node (ref "R6") (pin "1") (pinfunction "1_1") (pintype "passive"))
      (node (ref "U10") (pin "17") (pinfunction "PGEC1/AN6/RPI38/RB6_17") (pintype "passive"))
    )
    (net (code "10") (name "/GREEN") (class "Default")
      (node (ref "D2") (pin "2") (pinfunction "A_2") (pintype "passive"))
      (node (ref "U10") (pin "47") (pinfunction "PGED2/SOSCI/C3IN3-/RPI61/RC13_47") (pintype "passive"))
    )
    (net (code "11") (name "/LDO3.3V-5.0V") (class "Default")
      (node (ref "C1") (pin "1") (pinfunction "1_1") (pintype "passive"))
      (node (ref "R14") (pin "1") (pinfunction "1_1") (pintype "passive"))
      (node (ref "R15") (pin "1") (pinfunction "1_1") (pintype "passive"))
      (node (ref "U29") (pin "5") (pinfunction "CTL_5") (pintype "passive"))
      (node (ref "U29") (pin "8") (pinfunction "VCC_8") (pintype "passive"))
      (node (ref "U9") (pin "5") (pinfunction "CTL_5") (pintype "passive"))
      (node (ref "U9") (pin "8") (pinfunction "VCC_8") (pintype "passive"))
    )
    (net (code "12") (name "/LDO5.0V") (class "Default")
      (node (ref "C15") (pin "1") (pinfunction "1_1") (pintype "passive"))
      (node (ref "R15") (pin "2") (pinfunction "2_2") (pintype "passive"))
      (node (ref "R33") (pin "1") (pinfunction "1_1") (pintype "passive"))
      (node (ref "R34") (pin "2") (pinfunction "2_2") (pintype "passive"))
      (node (ref "U6") (pin "5") (pinfunction "CTL_5") (pintype "passive"))
      (node (ref "U6") (pin "8") (pinfunction "VCC_8") (pintype "passive"))
    )
    (net (code "13") (name "/LM12V") (class "Default")
      (node (ref "C592") (pin "1") (pinfunction "1_1") (pintype "passive"))
      (node (ref "D8") (pin "1") (pinfunction "C_1") (pintype "passive"))
      (node (ref "R13") (pin "1") (pinfunction "1_1") (pintype "passive"))
      (node (ref "U28") (pin "8") (pinfunction "INPUT_8") (pintype "passive"))
      (node (ref "U7") (pin "1") (pinfunction "Vin_1") (pintype "passive"))
      (node (ref "U8") (pin "1") (pinfunction "Vin_1") (pintype "passive"))
    )
    (net (code "14") (name "/MCLR") (class "Default")
      (node (ref "C5") (pin "1") (pinfunction "1_1") (pintype "passive"))
      (node (ref "J1") (pin "1") (pinfunction "1_1") (pintype "passive"))
      (node (ref "R31") (pin "1") (pinfunction "1_1") (pintype "passive"))
      (node (ref "U10") (pin "7") (pinfunction "~{MCLR}_7") (pintype "passive"))
    )
    (net (code "15") (name "/MCU5.0V") (class "Default")
      (node (ref "R32") (pin "2") (pinfunction "2_2") (pintype "passive"))
      (node (ref "U10") (pin "34") (pinfunction "VBUS_34") (pintype "passive"))
    )
    (net (code "16") (name "/Main OSC In") (class "Default")
      (node (ref "C10") (pin "1") (pinfunction "1_1") (pintype "passive"))
      (node (ref "U10") (pin "39") (pinfunction "OSC1/RPI60/RC12_39") (pintype "passive"))
      (node (ref "Y1") (pin "1") (pinfunction "1_1") (pintype "passive"))
    )
    (net (code "17") (name "/Main OSC Out") (class "Default")
      (node (ref "C11") (pin "1") (pinfunction "1_1") (pintype "passive"))
      (node (ref "U10") (pin "40") (pinfunction "OSC2/CLKO/RC15_40") (pintype "passive"))
      (node (ref "Y1") (pin "2") (pinfunction "2_2") (pintype "passive"))
    )
    (net (code "18") (name "/ORANGE") (class "Default")
      (node (ref "D4") (pin "2") (pinfunction "A_2") (pintype "passive"))
      (node (ref "U10") (pin "45") (pinfunction "PMCS1/RPI75/RD11_45") (pintype "passive"))
    )
    (net (code "19") (name "/PGC") (class "Default")
      (node (ref "J1") (pin "5") (pinfunction "5_5") (pintype "passive"))
      (node (ref "U10") (pin "15") (pinfunction "PGEC3/AN1/VREF-/RPI33/RB1_15") (pintype "passive"))
    )
    (net (code "20") (name "/PGD") (class "Default")
      (node (ref "J1") (pin "4") (pinfunction "4_4") (pintype "passive"))
      (node (ref "U10") (pin "16") (pinfunction "PGED3/AN0/VREF+/RPI32/RB0_16") (pintype "passive"))
    )
    (net (code "21") (name "/PWM1H") (class "Default")
      (node (ref "U10") (pin "61") (pinfunction "AN25/PWM1H/PMD1/RPI81/RE1_61") (pintype "passive"))
    )
    (net (code "22") (name "/PWM1L") (class "Default")
      (node (ref "U10") (pin "60") (pinfunction "AN24/PWM1L/PMD0/RP80/RE0_60") (pintype "passive"))
    )
    (net (code "23") (name "/PWM2H") (class "Default")
      (node (ref "U10") (pin "63") (pinfunction "AN27/PWM2H/PMD3/RPI83/RE3_63") (pintype "passive"))
    )
    (net (code "24") (name "/PWM2L") (class "Default")
      (node (ref "U10") (pin "62") (pinfunction "AN26/PWM2L/PMD2/RP82/RE2_62") (pintype "passive"))
    )
    (net (code "25") (name "/PWM3H") (class "Default")
      (node (ref "U10") (pin "1") (pinfunction "AN29/PWM3H/PMD5/RP85/RE5_1") (pintype "passive"))
    )
    (net (code "26") (name "/PWM3L") (class "Default")
      (node (ref "U10") (pin "64") (pinfunction "AN28/PWM3L/PMD4/RP84/RE4_64") (pintype "passive"))
    )
    (net (code "27") (name "/PWM4H") (class "Default")
      (node (ref "U10") (pin "3") (pinfunction "AN31/PWM4H/PMD7/RP87/RE7_3") (pintype "passive"))
    )
    (net (code "28") (name "/PWM4L") (class "Default")
      (node (ref "U10") (pin "2") (pinfunction "AN30/PWM4L/PMD6/RPI86/RE6_2") (pintype "passive"))
    )
    (net (code "29") (name "/RED") (class "Default")
      (node (ref "D1") (pin "2") (pinfunction "A_2") (pintype "passive"))
      (node (ref "U10") (pin "48") (pinfunction "PGEC2/SOSCO/C3IN1-/T1CK/RPI62/RC14_48") (pintype "passive"))
    )
    (net (code "30") (name "/RESET_ASIC") (class "Default")
      (node (ref "R26") (pin "2") (pinfunction "2_2") (pintype "passive"))
      (node (ref "U10") (pin "43") (pinfunction "ASDA1/DPLN/RPI73/RD9_43") (pintype "passive"))
    )
    (net (code "31") (name "/SPI_CS") (class "Default")
      (node (ref "U10") (pin "8") (pinfunction "C2IN1-/PMA2/RPI121/RG9_8") (pintype "passive"))
    )
    (net (code "32") (name "/SPI_MISO") (class "Default")
      (node (ref "U10") (pin "5") (pinfunction "C1IN1-/SDI2/PMA4/RPI119/RG7_5") (pintype "passive"))
    )
    (net (code "33") (name "/SPI_MOSI") (class "Default")
      (node (ref "U10") (pin "6") (pinfunction "C2IN3-/SDO2/PMA3/RP120/RG8_6") (pintype "passive"))
    )
    (net (code "34") (name "/SPI_SCK") (class "Default")
      (node (ref "U10") (pin "4") (pinfunction "C1IN3-/SCK2/PMA5/RP118/RG6_4") (pintype "passive"))
    )
    (net (code "35") (name "/USB5.0V") (class "Default")
      (node (ref "D6") (pin "4") (pinfunction "4_4") (pintype "passive"))
      (node (ref "D6") (pin "6") (pinfunction "6_6") (pintype "passive"))
      (node (ref "J2") (pin "1") (pinfunction "1_1") (pintype "passive"))
      (node (ref "R32") (pin "1") (pinfunction "1_1") (pintype "passive"))
      (node (ref "R33") (pin "2") (pinfunction "2_2") (pintype "passive"))
    )
    (net (code "36") (name "/VCAP") (class "Default")
      (node (ref "C2") (pin "1") (pinfunction "1_1") (pintype "passive"))
      (node (ref "U10") (pin "56") (pinfunction "VCAP_56") (pintype "passive"))
    )
    (net (code "37") (name "/YELLOW") (class "Default")
      (node (ref "D3") (pin "2") (pinfunction "A_2") (pintype "passive"))
      (node (ref "U10") (pin "44") (pinfunction "ASCL1/PMCS2/RPI74/RD10_44") (pintype "passive"))
    )
    (net (code "38") (name "GND") (class "Default")
      (node (ref "C1") (pin "2") (pinfunction "2_2") (pintype "passive"))
      (node (ref "C10") (pin "2") (pinfunction "2_2") (pintype "passive"))
      (node (ref "C11") (pin "2") (pinfunction "2_2") (pintype "passive"))
      (node (ref "C12") (pin "2") (pinfunction "2_2") (pintype "passive"))
      (node (ref "C13") (pin "1") (pinfunction "1_1") (pintype "passive"))
      (node (ref "C14") (pin "2") (pinfunction "2_2") (pintype "passive"))
      (node (ref "C15") (pin "2") (pinfunction "2_2") (pintype "passive"))
      (node (ref "C16") (pin "2") (pinfunction "2_2") (pintype "passive"))
      (node (ref "C17") (pin "2") (pinfunction "2_2") (pintype "passive"))
      (node (ref "C2") (pin "2") (pinfunction "2_2") (pintype "passive"))
      (node (ref "C231") (pin "2") (pinfunction "2_2") (pintype "passive"))
      (node (ref "C232") (pin "2") (pinfunction "2_2") (pintype "passive"))
      (node (ref "C3") (pin "2") (pinfunction "2_2") (pintype "passive"))
      (node (ref "C347") (pin "2") (pinfunction "2_2") (pintype "passive"))
      (node (ref "C5") (pin "2") (pinfunction "2_2") (pintype "passive"))
      (node (ref "C592") (pin "2") (pinfunction "2_2") (pintype "passive"))
      (node (ref "C6") (pin "2") (pinfunction "2_2") (pintype "passive"))
      (node (ref "C608") (pin "2") (pinfunction "2_2") (pintype "passive"))
      (node (ref "C7") (pin "2") (pinfunction "2_2") (pintype "passive"))
      (node (ref "C8") (pin "2") (pinfunction "2_2") (pintype "passive"))
      (node (ref "C9") (pin "2") (pinfunction "2_2") (pintype "passive"))
      (node (ref "D1") (pin "1") (pinfunction "C_1") (pintype "passive"))
      (node (ref "D2") (pin "1") (pinfunction "C_1") (pintype "passive"))
      (node (ref "D26") (pin "2") (pinfunction "A_2") (pintype "passive"))
      (node (ref "D28") (pin "2") (pinfunction "A_2") (pintype "passive"))
      (node (ref "D3") (pin "1") (pinfunction "C_1") (pintype "passive"))
      (node (ref "D30") (pin "2") (pinfunction "A_2") (pintype "passive"))
      (node (ref "D32") (pin "2") (pinfunction "A_2") (pintype "passive"))
      (node (ref "D4") (pin "1") (pinfunction "C_1") (pintype "passive"))
      (node (ref "D6") (pin "2") (pinfunction "2_2") (pintype "passive"))
      (node (ref "D6") (pin "5") (pinfunction "5_5") (pintype "passive"))
      (node (ref "J1") (pin "3") (pinfunction "3_3") (pintype "passive"))
      (node (ref "J13") (pin "1") (pinfunction "1_1") (pintype "passive"))
      (node (ref "J14") (pin "1") (pinfunction "1_1") (pintype "passive"))
      (node (ref "J15") (pin "1") (pinfunction "1_1") (pintype "passive"))
      (node (ref "J16") (pin "1") (pinfunction "1_1") (pintype "passive"))
      (node (ref "J17") (pin "1") (pinfunction "1_1") (pintype "passive"))
      (node (ref "J18") (pin "1") (pinfunction "1_1") (pintype "passive"))
      (node (ref "J19") (pin "1") (pinfunction "1_1") (pintype "passive"))
      (node (ref "J2") (pin "5") (pinfunction "5_5") (pintype "passive"))
      (node (ref "J2") (pin "6") (pinfunction "6_6") (pintype "passive"))
      (node (ref "J2") (pin "7") (pinfunction "7_7") (pintype "passive"))
      (node (ref "J2") (pin "8") (pinfunction "8_8") (pintype "passive"))
      (node (ref "J2") (pin "9") (pinfunction "9_9") (pintype "passive"))
      (node (ref "J20") (pin "1") (pinfunction "1_1") (pintype "passive"))
      (node (ref "J21") (pin "1") (pinfunction "1_1") (pintype "passive"))
      (node (ref "J22") (pin "1") (pinfunction "1_1") (pintype "passive"))
      (node (ref "J23") (pin "1") (pinfunction "1_1") (pintype "passive"))
      (node (ref "J24") (pin "1") (pinfunction "1_1") (pintype "passive"))
      (node (ref "J3") (pin "2") (pinfunction "2_2") (pintype "passive"))
      (node (ref "J4") (pin "4") (pinfunction "4_4") (pintype "passive"))
      (node (ref "J4") (pin "5") (pinfunction "5_5") (pintype "passive"))
      (node (ref "J4") (pin "6") (pinfunction "6_6") (pintype "passive"))
      (node (ref "J5") (pin "4") (pinfunction "4_4") (pintype "passive"))
      (node (ref "J5") (pin "5") (pinfunction "5_5") (pintype "passive"))
      (node (ref "J5") (pin "6") (pinfunction "6_6") (pintype "passive"))
      (node (ref "J6") (pin "4") (pinfunction "4_4") (pintype "passive"))
      (node (ref "J6") (pin "5") (pinfunction "5_5") (pintype "passive"))
      (node (ref "J6") (pin "6") (pinfunction "6_6") (pintype "passive"))
      (node (ref "J7") (pin "4") (pinfunction "4_4") (pintype "passive"))
      (node (ref "J7") (pin "5") (pinfunction "5_5") (pintype "passive"))
      (node (ref "J7") (pin "6") (pinfunction "6_6") (pintype "passive"))
      (node (ref "J9") (pin "1") (pinfunction "1_1") (pintype "passive"))
      (node (ref "R17") (pin "2") (pinfunction "2_2") (pintype "passive"))
      (node (ref "R28") (pin "2") (pinfunction "2_2") (pintype "passive"))
      (node (ref "U10") (pin "20") (pinfunction "AVSS_20") (pintype "passive"))
      (node (ref "U10") (pin "25") (pinfunction "VSS_25") (pintype "passive"))
      (node (ref "U10") (pin "41") (pinfunction "VSS_41") (pintype "passive"))
      (node (ref "U10") (pin "9") (pinfunction "VSS_9") (pintype "passive"))
      (node (ref "U28") (pin "2") (pinfunction "GND_2") (pintype "passive"))
      (node (ref "U28") (pin "3") (pinfunction "GND_3") (pintype "passive"))
      (node (ref "U28") (pin "4") (pinfunction "N.C._4") (pintype "passive"))
      (node (ref "U28") (pin "5") (pinfunction "N.C._5") (pintype "passive"))
      (node (ref "U28") (pin "6") (pinfunction "GND_6") (pintype "passive"))
      (node (ref "U28") (pin "7") (pinfunction "GND_7") (pintype "passive"))
      (node (ref "U29") (pin "6") (pinfunction "GND_6") (pintype "passive"))
      (node (ref "U29") (pin "7") (pinfunction "GND_7") (pintype "passive"))
      (node (ref "U6") (pin "6") (pinfunction "GND_6") (pintype "passive"))
      (node (ref "U6") (pin "7") (pinfunction "GND_7") (pintype "passive"))
      (node (ref "U7") (pin "4") (pinfunction "GND_4") (pintype "passive"))
      (node (ref "U8") (pin "4") (pinfunction "GND_4") (pintype "passive"))
      (node (ref "U9") (pin "6") (pinfunction "GND_6") (pintype "passive"))
      (node (ref "U9") (pin "7") (pinfunction "GND_7") (pintype "passive"))
    )
    (net (code "39") (name "Net-(U9-ADJ)") (class "Default")
      (node (ref "R16") (pin "2") (pinfunction "2_2") (pintype "passive"))
      (node (ref "R17") (pin "1") (pinfunction "1_1") (pintype "passive"))
      (node (ref "U9") (pin "2") (pinfunction "ADJ_2") (pintype "passive"))
    )
    (net (code "40") (name "Net-(U10-AN2{slash}C2IN2-{slash}VMIO{slash}RPI34{slash}RB2)") (class "Default")
      (node (ref "TP7") (pin "1") (pinfunction "1_1") (pintype "passive"))
      (node (ref "U10") (pin "14") (pinfunction "AN2/C2IN2-/VMIO/RPI34/RB2_14") (pintype "passive"))
    )
    (net (code "41") (name "Net-(U10-AN3{slash}C2IN1+{slash}VPIO{slash}RPI35{slash}RB3)") (class "Default")
      (node (ref "TP6") (pin "1") (pinfunction "1_1") (pintype "passive"))
      (node (ref "U10") (pin "13") (pinfunction "AN3/C2IN1+/VPIO/RPI35/RB3_13") (pintype "passive"))
    )
    (net (code "42") (name "Net-(U10-AN4{slash}C1IN2-{slash}USBOEN{slash}RPI36{slash}RB4)") (class "Default")
      (node (ref "TP5") (pin "1") (pinfunction "1_1") (pintype "passive"))
      (node (ref "U10") (pin "12") (pinfunction "AN4/C1IN2-/USBOEN/RPI36/RB4_12") (pintype "passive"))
    )
    (net (code "43") (name "Net-(U10-AN5{slash}C1IN1+{slash}VBUSON{slash}VBUSST{slash}RPI37{slash}RB5)") (class "Default")
      (node (ref "TP128") (pin "1") (pinfunction "1_1") (pintype "passive"))
      (node (ref "U10") (pin "11") (pinfunction "AN5/C1IN1+/VBUSON/VBUSST/RPI37/RB5_11") (pintype "passive"))
    )
    (net (code "44") (name "Net-(U10-AN8{slash}PMA6{slash}RPI40{slash}RB8)") (class "Default")
      (node (ref "TP10") (pin "1") (pinfunction "1_1") (pintype "passive"))
      (node (ref "U10") (pin "21") (pinfunction "AN8/PMA6/RPI40/RB8_21") (pintype "passive"))
    )
    (net (code "45") (name "Net-(U10-AN9{slash}PMA7{slash}{slash}RPI41{slash}RB9)") (class "Default")
      (node (ref "TP11") (pin "1") (pinfunction "1_1") (pintype "passive"))
      (node (ref "U10") (pin "22") (pinfunction "AN9/PMA7//RPI41/RB9_22") (pintype "passive"))
    )
    (net (code "46") (name "Net-(U10-AN14{slash}PMA1{slash}RPI46{slash}RB14)") (class "Default")
      (node (ref "TP124") (pin "1") (pinfunction "1_1") (pintype "passive"))
      (node (ref "U10") (pin "29") (pinfunction "AN14/PMA1/RPI46/RB14_29") (pintype "passive"))
    )
    (net (code "47") (name "Net-(U10-AN15{slash}PMA0{slash}RPI47{slash}RB15)") (class "Default")
      (node (ref "TP125") (pin "1") (pinfunction "1_1") (pintype "passive"))
      (node (ref "U10") (pin "30") (pinfunction "AN15/PMA0/RPI47/RB15_30") (pintype "passive"))
    )
    (net (code "48") (name "Net-(U10-C3IN1+{slash}VCMPST3{slash}RP71{slash}RD7)") (class "Default")
      (node (ref "TP18") (pin "1") (pinfunction "1_1") (pintype "passive"))
      (node (ref "U10") (pin "55") (pinfunction "C3IN1+/VCMPST3/RP71/RD7_55") (pintype "passive"))
    )
    (net (code "49") (name "Net-(U10-C3IN2-{slash}RP70{slash}RD6)") (class "Default")
      (node (ref "TP19") (pin "1") (pinfunction "1_1") (pintype "passive"))
      (node (ref "U10") (pin "54") (pinfunction "C3IN2-/RP70/RD6_54") (pintype "passive"))
    )
    (net (code "50") (name "Net-(U10-DPH{slash}RP66{slash}RD2)") (class "Default")
      (node (ref "TP22") (pin "1") (pinfunction "1_1") (pintype "passive"))
      (node (ref "U10") (pin "50") (pinfunction "DPH/RP66/RD2_50") (pintype "passive"))
    )
    (net (code "51") (name "Net-(U10-INT0{slash}DMH{slash}RP64{slash}RD0)") (class "Default")
      (node (ref "TP24") (pin "1") (pinfunction "1_1") (pintype "passive"))
      (node (ref "U10") (pin "46") (pinfunction "INT0/DMH/RP64/RD0_46") (pintype "passive"))
    )
    (net (code "52") (name "Net-(U10-PGED1{slash}AN7{slash}RCV{slash}RPI39{slash}RB7)") (class "Default")
      (node (ref "TP26") (pin "1") (pinfunction "1_1") (pintype "passive"))
      (node (ref "U10") (pin "18") (pinfunction "PGED1/AN7/RCV/RPI39/RB7_18") (pintype "passive"))
    )
    (net (code "53") (name "Net-(U10-PMBE{slash}RP67{slash}RD3)") (class "Default")
      (node (ref "TP17") (pin "1") (pinfunction "1_1") (pintype "passive"))
      (node (ref "U10") (pin "51") (pinfunction "PMBE/RP67/RD3_51") (pintype "passive"))
    )
    (net (code "54") (name "Net-(U10-PMRD{slash}RP69{slash}RD5)") (class "Default")
      (node (ref "TP25") (pin "1") (pinfunction "1_1") (pintype "passive"))
      (node (ref "U10") (pin "53") (pinfunction "PMRD/RP69/RD5_53") (pintype "passive"))
    )
    (net (code "55") (name "Net-(U10-PMWR{slash}RP68{slash}RD4)") (class "Default")
      (node (ref "TP20") (pin "1") (pinfunction "1_1") (pintype "passive"))
      (node (ref "U10") (pin "52") (pinfunction "PMWR/RP68/RD4_52") (pintype "passive"))
    )
    (net (code "56") (name "Net-(U10-RTCC{slash}DMLN{slash}RPI72{slash}RD8)") (class "Default")
      (node (ref "TP13") (pin "1") (pinfunction "1_1") (pintype "passive"))
      (node (ref "U10") (pin "42") (pinfunction "RTCC/DMLN/RPI72/RD8_42") (pintype "passive"))
    )
    (net (code "57") (name "Net-(U10-SCL2{slash}PMA8{slash}RP101{slash}RF5)") (class "Default")
      (node (ref "TP127") (pin "1") (pinfunction "1_1") (pintype "passive"))
      (node (ref "U10") (pin "32") (pinfunction "SCL2/PMA8/RP101/RF5_32") (pintype "passive"))
    )
    (net (code "58") (name "Net-(U10-SDA2{slash}PMA9{slash}RP100{slash}RF4)") (class "Default")
      (node (ref "TP126") (pin "1") (pinfunction "1_1") (pintype "passive"))
      (node (ref "U10") (pin "31") (pinfunction "SDA2/PMA9/RP100/RF4_31") (pintype "passive"))
    )
    (net (code "59") (name "Net-(U10-TCK{slash}AN12{slash}PMA11{slash}RPI44{slash}RB12)") (class "Default")
      (node (ref "TP2") (pin "1") (pinfunction "1_1") (pintype "passive"))
      (node (ref "U10") (pin "27") (pinfunction "TCK/AN12/PMA11/RPI44/RB12_27") (pintype "passive"))
    )
    (net (code "60") (name "Net-(U10-TDI{slash}AN13{slash}PMA10{slash}RPI45{slash}RB13)") (class "Default")
      (node (ref "TP123") (pin "1") (pinfunction "1_1") (pintype "passive"))
      (node (ref "U10") (pin "28") (pinfunction "TDI/AN13/PMA10/RPI45/RB13_28") (pintype "passive"))
    )
    (net (code "61") (name "Net-(U10-TDO{slash}AN11{slash}PMA12{slash}RPI43{slash}RB11)") (class "Default")
      (node (ref "TP132") (pin "1") (pinfunction "1_1") (pintype "passive"))
      (node (ref "U10") (pin "24") (pinfunction "TDO/AN11/PMA12/RPI43/RB11_24") (pintype "passive"))
    )
    (net (code "62") (name "Net-(U10-TMS{slash}AN10{slash}CVREF{slash}PMA13{slash}RPI42{slash}RB10)") (class "Default")
      (node (ref "TP131") (pin "1") (pinfunction "1_1") (pintype "passive"))
      (node (ref "U10") (pin "23") (pinfunction "TMS/AN10/CVREF/PMA13/RPI42/RB10_23") (pintype "passive"))
    )
    (net (code "63") (name "Net-(U10-USBID{slash}RP99{slash}RF3)") (class "Default")
      (node (ref "TP21") (pin "1") (pinfunction "1_1") (pintype "passive"))
      (node (ref "U10") (pin "33") (pinfunction "USBID/RP99/RF3_33") (pintype "passive"))
    )
    (net (code "64") (name "Net-(U10-VCMPST1{slash}RP96{slash}RF0)") (class "Default")
      (node (ref "TP12") (pin "1") (pinfunction "1_1") (pintype "passive"))
      (node (ref "U10") (pin "58") (pinfunction "VCMPST1/RP96/RF0_58") (pintype "passive"))
    )
    (net (code "65") (name "Net-(U10-VCMPST2{slash}RP97{slash}RF1)") (class "Default")
      (node (ref "TP129") (pin "1") (pinfunction "1_1") (pintype "passive"))
      (node (ref "U10") (pin "59") (pinfunction "VCMPST2/RP97/RF1_59") (pintype "passive"))
    )
    (net (code "66") (name "Net-(U10-VCPCON{slash}RP65{slash}RD1)") (class "Default")
      (node (ref "TP23") (pin "1") (pinfunction "1_1") (pintype "passive"))
      (node (ref "U10") (pin "49") (pinfunction "VCPCON/RP65/RD1_49") (pintype "passive"))
    )
    (net (code "67") (name "Net-(U29-ADJ)") (class "Default")
      (node (ref "R27") (pin "2") (pinfunction "2_2") (pintype "passive"))
      (node (ref "R28") (pin "1") (pinfunction "1_1") (pintype "passive"))
      (node (ref "U29") (pin "2") (pinfunction "ADJ_2") (pintype "passive"))
    )
    (net (code "68") (name "unconnected-(J2-Pad4)") (class "Default")
      (node (ref "J2") (pin "4") (pinfunction "4_4") (pintype "passive+no_connect"))
    )
    (net (code "69") (name "unconnected-(U6-NC-Pad2)") (class "Default")
      (node (ref "U6") (pin "2") (pinfunction "NC_2") (pintype "passive+no_connect"))
    )
    (net (code "70") (name "unconnected-(U6-NC-Pad3)") (class "Default")
      (node (ref "U6") (pin "3") (pinfunction "NC_3") (pintype "passive+no_connect"))
    )
    (net (code "71") (name "unconnected-(U6-NC-Pad4)") (class "Default")
      (node (ref "U6") (pin "4") (pinfunction "NC_4") (pintype "passive+no_connect"))
    )
    (net (code "72") (name "unconnected-(U9-NC-Pad3)") (class "Default")
      (node (ref "U9") (pin "3") (pinfunction "NC_3") (pintype "passive+no_connect"))
    )
    (net (code "73") (name "unconnected-(U9-NC-Pad4)") (class "Default")
      (node (ref "U9") (pin "4") (pinfunction "NC_4") (pintype "passive+no_connect"))
    )
    (net (code "74") (name "unconnected-(U29-NC-Pad3)") (class "Default")
      (node (ref "U29") (pin "3") (pinfunction "NC_3") (pintype "passive+no_connect"))
    )
    (net (code "75") (name "unconnected-(U29-NC-Pad4)") (class "Default")
      (node (ref "U29") (pin "4") (pinfunction "NC_4") (pintype "passive+no_connect"))
    )
  )
)
